# loop-rs232o.net
KiCad netlist of a schematic drawn in EAGLE
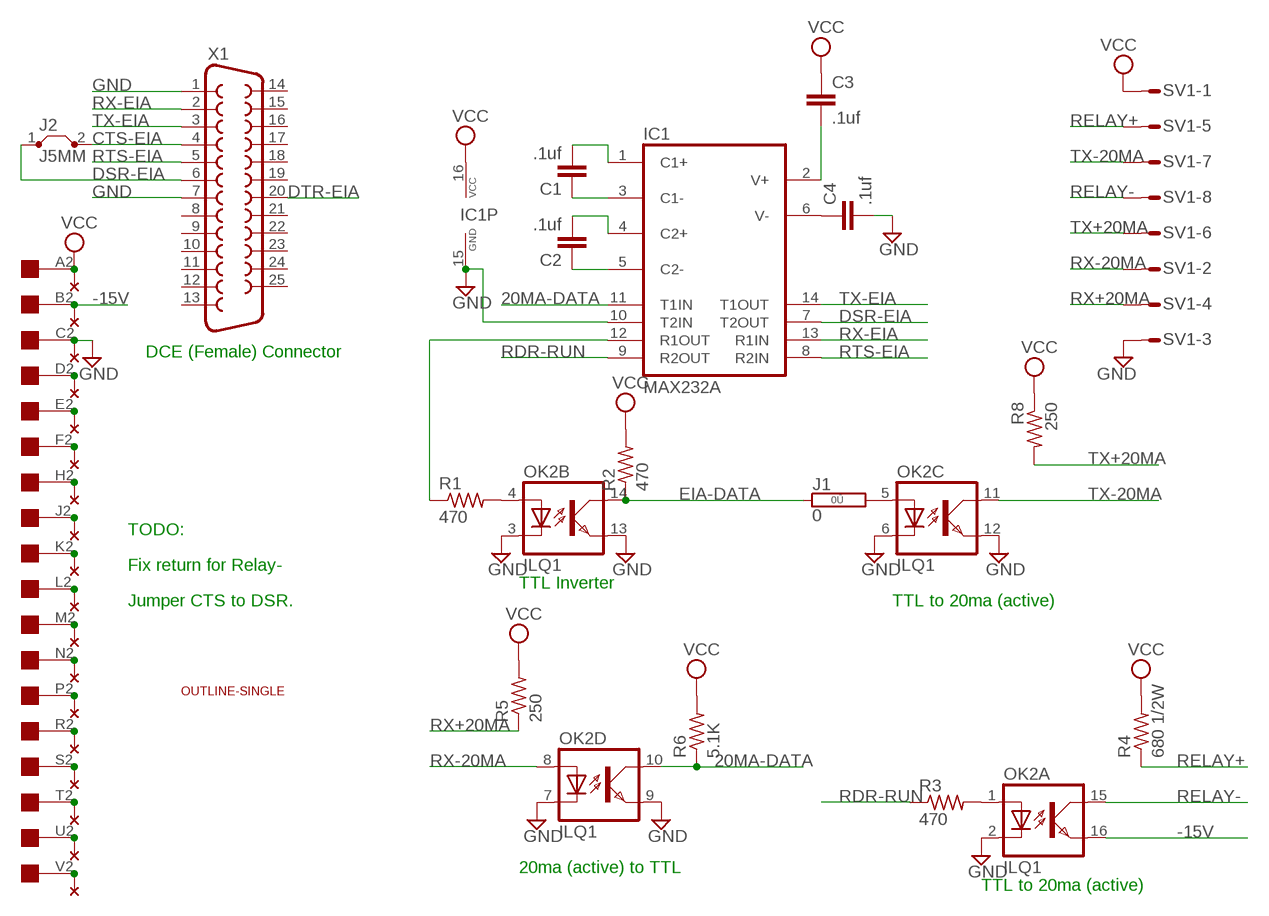
[diagram p0: schematic, sheet 1]

(export (version "E")
  (design (tool "Eeschema 10.0.6"))
  (components
    (comp (ref "C1")
      (value ".1uf")
      (footprint "eagle-import:C050-025X075")
      (libsource (lib "eagle-import") (part "C-EU050-025X075"))
    )
    (comp (ref "C2")
      (value ".1uf")
      (footprint "eagle-import:C050-025X075")
      (libsource (lib "eagle-import") (part "C-EU050-025X075"))
    )
    (comp (ref "C3")
      (value ".1uf")
      (footprint "eagle-import:C050-025X075")
      (libsource (lib "eagle-import") (part "C-EU050-025X075"))
    )
    (comp (ref "C4")
      (value ".1uf")
      (footprint "eagle-import:C050-025X075")
      (libsource (lib "eagle-import") (part "C-EU050-025X075"))
    )
    (comp (ref "IC1")
      (value "MAX232A")
      (footprint "eagle-import:DIL16")
      (fields (field (name "MF") "MAXIM") (field (name "MPN") "MAX232ACPE+"))
      (libsource (lib "eagle-import") (part "MAX232"))
    )
    (comp (ref "J1")
      (value "0")
      (footprint "eagle-import:0R_10")
      (libsource (lib "eagle-import") (part "0R"))
    )
    (comp (ref "J2")
      (value "J5MM")
      (footprint "eagle-import:05")
      (libsource (lib "eagle-import") (part "J5MM"))
    )
    (comp (ref "OK2")
      (value "ILQ1")
      (footprint "eagle-import:DIL16")
      (fields (field (name "MF") "VISHAY/TELEFUNKEN"))
      (libsource (lib "eagle-import") (part "ILQ1"))
    )
    (comp (ref "R1")
      (value "470")
      (footprint "eagle-import:0207_10")
      (libsource (lib "eagle-import") (part "R-US_0207/10"))
    )
    (comp (ref "R2")
      (value "470")
      (footprint "eagle-import:0207_10")
      (libsource (lib "eagle-import") (part "R-US_0207/10"))
    )
    (comp (ref "R3")
      (value "470")
      (footprint "eagle-import:0207_10")
      (libsource (lib "eagle-import") (part "R-US_0207/10"))
    )
    (comp (ref "R4")
      (value "680 1/2W")
      (footprint "eagle-import:0207_10")
      (libsource (lib "eagle-import") (part "R-US_0207/10"))
    )
    (comp (ref "R5")
      (value "250")
      (footprint "eagle-import:0207_10")
      (libsource (lib "eagle-import") (part "R-US_0207/10"))
    )
    (comp (ref "R6")
      (value "5.1K")
      (footprint "eagle-import:0207_10")
      (libsource (lib "eagle-import") (part "R-US_0207/10"))
    )
    (comp (ref "R8")
      (value "250")
      (footprint "eagle-import:0207_10")
      (libsource (lib "eagle-import") (part "R-US_0207/10"))
    )
    (comp (ref "SV1")
      (value "S08P")
      (footprint "eagle-import:S08P")
      (libsource (lib "eagle-import") (part "S08P"))
    )
    (comp (ref "U$2")
      (value "THRU-HOLE1")
      (footprint "eagle-import:THRU-HOLE1")
      (libsource (lib "eagle-import") (part "THRU-HOLE1"))
    )
    (comp (ref "U$3")
      (value "OUTLINE-SINGLE")
      (footprint "eagle-import:SINGLE")
      (libsource (lib "eagle-import") (part "OUTLINE-SINGLE"))
    )
    (comp (ref "U$4")
      (value "EDGE-1")
      (footprint "eagle-import:EDGE-CON1")
      (libsource (lib "eagle-import") (part "EDGE-1"))
    )
    (comp (ref "X1")
      (value "F25H")
      (footprint "eagle-import:F25H")
      (libsource (lib "eagle-import") (part "F25H"))
    )
  )
  (nets
    (net (code "1") (name "/-15V") (class "Default")
      (node (ref "OK2") (pin "16") (pinfunction "EMIT_16") (pintype "passive"))
      (node (ref "U$2") (pin "B2") (pinfunction "P$1_B2") (pintype "passive"))
      (node (ref "U$4") (pin "B2") (pinfunction "1_B2") (pintype "bidirectional"))
    )
    (net (code "2") (name "/20MA-DATA") (class "Default")
      (node (ref "IC1") (pin "11") (pinfunction "T1IN_11") (pintype "input"))
      (node (ref "OK2") (pin "10") (pinfunction "COL_10") (pintype "passive"))
      (node (ref "R6") (pin "1") (pinfunction "1_1") (pintype "passive"))
    )
    (net (code "3") (name "/CTS-EIA") (class "Default")
      (node (ref "J2") (pin "2") (pinfunction "2_2") (pintype "passive"))
      (node (ref "X1") (pin "4") (pinfunction "4_4") (pintype "passive"))
    )
    (net (code "4") (name "/DSR-EIA") (class "Default")
      (node (ref "IC1") (pin "7") (pinfunction "T2OUT_7") (pintype "output"))
      (node (ref "J2") (pin "1") (pinfunction "1_1") (pintype "passive"))
      (node (ref "X1") (pin "6") (pinfunction "6_6") (pintype "passive"))
    )
    (net (code "5") (name "/DTR-EIA") (class "Default")
      (node (ref "X1") (pin "20") (pinfunction "20_20") (pintype "passive"))
    )
    (net (code "6") (name "/EIA-DATA") (class "Default")
      (node (ref "J1") (pin "1") (pinfunction "1_1") (pintype "passive"))
      (node (ref "OK2") (pin "14") (pinfunction "COL_14") (pintype "passive"))
      (node (ref "R2") (pin "1") (pinfunction "1_1") (pintype "passive"))
    )
    (net (code "7") (name "/RDR-RUN") (class "Default")
      (node (ref "IC1") (pin "9") (pinfunction "R2OUT_9") (pintype "output"))
      (node (ref "R3") (pin "1") (pinfunction "1_1") (pintype "passive"))
    )
    (net (code "8") (name "/RELAY+") (class "Default")
      (node (ref "R4") (pin "1") (pinfunction "1_1") (pintype "passive"))
      (node (ref "SV1") (pin "5") (pinfunction "S_5") (pintype "passive"))
    )
    (net (code "9") (name "/RELAY-") (class "Default")
      (node (ref "OK2") (pin "15") (pinfunction "COL_15") (pintype "passive"))
      (node (ref "SV1") (pin "8") (pinfunction "S_8") (pintype "passive"))
    )
    (net (code "10") (name "/RTS-EIA") (class "Default")
      (node (ref "IC1") (pin "8") (pinfunction "R2IN_8") (pintype "input"))
      (node (ref "X1") (pin "5") (pinfunction "5_5") (pintype "passive"))
    )
    (net (code "11") (name "/RX+20MA") (class "Default")
      (node (ref "R5") (pin "1") (pinfunction "1_1") (pintype "passive"))
      (node (ref "SV1") (pin "4") (pinfunction "S_4") (pintype "passive"))
    )
    (net (code "12") (name "/RX-20MA") (class "Default")
      (node (ref "OK2") (pin "8") (pinfunction "A_8") (pintype "passive"))
      (node (ref "SV1") (pin "2") (pinfunction "S_2") (pintype "passive"))
    )
    (net (code "13") (name "/RX-EIA") (class "Default")
      (node (ref "IC1") (pin "13") (pinfunction "R1IN_13") (pintype "input"))
      (node (ref "X1") (pin "2") (pinfunction "2_2") (pintype "passive"))
    )
    (net (code "14") (name "/TX+20MA") (class "Default")
      (node (ref "R8") (pin "2") (pinfunction "2_2") (pintype "passive"))
      (node (ref "SV1") (pin "6") (pinfunction "S_6") (pintype "passive"))
    )
    (net (code "15") (name "/TX-20MA") (class "Default")
      (node (ref "OK2") (pin "11") (pinfunction "COL_11") (pintype "passive"))
      (node (ref "SV1") (pin "7") (pinfunction "S_7") (pintype "passive"))
    )
    (net (code "16") (name "/TX-EIA") (class "Default")
      (node (ref "IC1") (pin "14") (pinfunction "T1OUT_14") (pintype "output"))
      (node (ref "X1") (pin "3") (pinfunction "3_3") (pintype "passive"))
    )
    (net (code "17") (name "GND") (class "Default")
      (node (ref "C4") (pin "2") (pinfunction "2_2") (pintype "passive"))
      (node (ref "IC1") (pin "10") (pinfunction "T2IN_10") (pintype "input"))
      (node (ref "IC1") (pin "15") (pinfunction "GND_15") (pintype "power_in"))
      (node (ref "OK2") (pin "12") (pinfunction "EMIT_12") (pintype "passive"))
      (node (ref "OK2") (pin "13") (pinfunction "EMIT_13") (pintype "passive"))
      (node (ref "OK2") (pin "2") (pinfunction "C_2") (pintype "passive"))
      (node (ref "OK2") (pin "3") (pinfunction "C_3") (pintype "passive"))
      (node (ref "OK2") (pin "6") (pinfunction "C_6") (pintype "passive"))
      (node (ref "OK2") (pin "7") (pinfunction "C_7") (pintype "passive"))
      (node (ref "OK2") (pin "9") (pinfunction "EMIT_9") (pintype "passive"))
      (node (ref "SV1") (pin "3") (pinfunction "S_3") (pintype "passive"))
      (node (ref "U$2") (pin "C2") (pinfunction "P$1_C2") (pintype "passive"))
      (node (ref "U$4") (pin "C2") (pinfunction "1_C2") (pintype "bidirectional"))
      (node (ref "X1") (pin "1") (pinfunction "1_1") (pintype "passive"))
      (node (ref "X1") (pin "7") (pinfunction "7_7") (pintype "passive"))
    )
    (net (code "18") (name "Net-(IC1A-C1+)") (class "Default")
      (node (ref "C1") (pin "2") (pinfunction "2_2") (pintype "passive"))
      (node (ref "IC1") (pin "1") (pinfunction "C1+_1") (pintype "bidirectional"))
    )
    (net (code "19") (name "Net-(IC1A-C1-)") (class "Default")
      (node (ref "C1") (pin "1") (pinfunction "1_1") (pintype "passive"))
      (node (ref "IC1") (pin "3") (pinfunction "C1-_3") (pintype "bidirectional"))
    )
    (net (code "20") (name "Net-(IC1A-C2+)") (class "Default")
      (node (ref "C2") (pin "2") (pinfunction "2_2") (pintype "passive"))
      (node (ref "IC1") (pin "4") (pinfunction "C2+_4") (pintype "bidirectional"))
    )
    (net (code "21") (name "Net-(IC1A-C2-)") (class "Default")
      (node (ref "C2") (pin "1") (pinfunction "1_1") (pintype "passive"))
      (node (ref "IC1") (pin "5") (pinfunction "C2-_5") (pintype "bidirectional"))
    )
    (net (code "22") (name "Net-(IC1A-R1OUT)") (class "Default")
      (node (ref "IC1") (pin "12") (pinfunction "R1OUT_12") (pintype "output"))
      (node (ref "R1") (pin "1") (pinfunction "1_1") (pintype "passive"))
    )
    (net (code "23") (name "Net-(IC1A-V+)") (class "Default")
      (node (ref "C3") (pin "2") (pinfunction "2_2") (pintype "passive"))
      (node (ref "IC1") (pin "2") (pinfunction "V+_2") (pintype "bidirectional"))
    )
    (net (code "24") (name "Net-(IC1A-V-)") (class "Default")
      (node (ref "C4") (pin "1") (pinfunction "1_1") (pintype "passive"))
      (node (ref "IC1") (pin "6") (pinfunction "V-_6") (pintype "bidirectional"))
    )
    (net (code "25") (name "Net-(OK2A-A)") (class "Default")
      (node (ref "OK2") (pin "1") (pinfunction "A_1") (pintype "passive"))
      (node (ref "R3") (pin "2") (pinfunction "2_2") (pintype "passive"))
    )
    (net (code "26") (name "Net-(OK2B-A)") (class "Default")
      (node (ref "OK2") (pin "4") (pinfunction "A_4") (pintype "passive"))
      (node (ref "R1") (pin "2") (pinfunction "2_2") (pintype "passive"))
    )
    (net (code "27") (name "Net-(OK2C-A)") (class "Default")
      (node (ref "J1") (pin "2") (pinfunction "2_2") (pintype "passive"))
      (node (ref "OK2") (pin "5") (pinfunction "A_5") (pintype "passive"))
    )
    (net (code "28") (name "Net-(U$2D-P$1)") (class "Default")
      (node (ref "U$2") (pin "D2") (pinfunction "P$1_D2") (pintype "passive"))
      (node (ref "U$4") (pin "D2") (pinfunction "1_D2") (pintype "bidirectional"))
    )
    (net (code "29") (name "Net-(U$2E-P$1)") (class "Default")
      (node (ref "U$2") (pin "E2") (pinfunction "P$1_E2") (pintype "passive"))
      (node (ref "U$4") (pin "E2") (pinfunction "1_E2") (pintype "bidirectional"))
    )
    (net (code "30") (name "Net-(U$2F-P$1)") (class "Default")
      (node (ref "U$2") (pin "F2") (pinfunction "P$1_F2") (pintype "passive"))
      (node (ref "U$4") (pin "F2") (pinfunction "1_F2") (pintype "bidirectional"))
    )
    (net (code "31") (name "Net-(U$2G-P$1)") (class "Default")
      (node (ref "U$2") (pin "H2") (pinfunction "P$1_H2") (pintype "passive"))
      (node (ref "U$4") (pin "H2") (pinfunction "1_H2") (pintype "bidirectional"))
    )
    (net (code "32") (name "Net-(U$2H-P$1)") (class "Default")
      (node (ref "U$2") (pin "J2") (pinfunction "P$1_J2") (pintype "passive"))
      (node (ref "U$4") (pin "J2") (pinfunction "1_J2") (pintype "bidirectional"))
    )
    (net (code "33") (name "Net-(U$2I-P$1)") (class "Default")
      (node (ref "U$2") (pin "K2") (pinfunction "P$1_K2") (pintype "passive"))
      (node (ref "U$4") (pin "K2") (pinfunction "1_K2") (pintype "bidirectional"))
    )
    (net (code "34") (name "Net-(U$2J-P$1)") (class "Default")
      (node (ref "U$2") (pin "L2") (pinfunction "P$1_L2") (pintype "passive"))
      (node (ref "U$4") (pin "L2") (pinfunction "1_L2") (pintype "bidirectional"))
    )
    (net (code "35") (name "Net-(U$2K-P$1)") (class "Default")
      (node (ref "U$2") (pin "M2") (pinfunction "P$1_M2") (pintype "passive"))
      (node (ref "U$4") (pin "M2") (pinfunction "1_M2") (pintype "bidirectional"))
    )
    (net (code "36") (name "Net-(U$2L-P$1)") (class "Default")
      (node (ref "U$2") (pin "N2") (pinfunction "P$1_N2") (pintype "passive"))
      (node (ref "U$4") (pin "N2") (pinfunction "1_N2") (pintype "bidirectional"))
    )
    (net (code "37") (name "Net-(U$2M-P$1)") (class "Default")
      (node (ref "U$2") (pin "P2") (pinfunction "P$1_P2") (pintype "passive"))
      (node (ref "U$4") (pin "P2") (pinfunction "1_P2") (pintype "bidirectional"))
    )
    (net (code "38") (name "Net-(U$2N-P$1)") (class "Default")
      (node (ref "U$2") (pin "R2") (pinfunction "P$1_R2") (pintype "passive"))
      (node (ref "U$4") (pin "R2") (pinfunction "1_R2") (pintype "bidirectional"))
    )
    (net (code "39") (name "Net-(U$2O-P$1)") (class "Default")
      (node (ref "U$2") (pin "S2") (pinfunction "P$1_S2") (pintype "passive"))
      (node (ref "U$4") (pin "S2") (pinfunction "1_S2") (pintype "bidirectional"))
    )
    (net (code "40") (name "Net-(U$2P-P$1)") (class "Default")
      (node (ref "U$2") (pin "T2") (pinfunction "P$1_T2") (pintype "passive"))
      (node (ref "U$4") (pin "T2") (pinfunction "1_T2") (pintype "bidirectional"))
    )
    (net (code "41") (name "Net-(U$2Q-P$1)") (class "Default")
      (node (ref "U$2") (pin "U2") (pinfunction "P$1_U2") (pintype "passive"))
      (node (ref "U$4") (pin "U2") (pinfunction "1_U2") (pintype "bidirectional"))
    )
    (net (code "42") (name "Net-(U$2R-P$1)") (class "Default")
      (node (ref "U$2") (pin "V2") (pinfunction "P$1_V2") (pintype "passive"))
      (node (ref "U$4") (pin "V2") (pinfunction "1_V2") (pintype "bidirectional"))
    )
    (net (code "43") (name "VCC") (class "Default")
      (node (ref "C3") (pin "1") (pinfunction "1_1") (pintype "passive"))
      (node (ref "IC1") (pin "16") (pinfunction "VCC_16") (pintype "power_in"))
      (node (ref "R2") (pin "2") (pinfunction "2_2") (pintype "passive"))
      (node (ref "R4") (pin "2") (pinfunction "2_2") (pintype "passive"))
      (node (ref "R5") (pin "2") (pinfunction "2_2") (pintype "passive"))
      (node (ref "R6") (pin "2") (pinfunction "2_2") (pintype "passive"))
      (node (ref "R8") (pin "1") (pinfunction "1_1") (pintype "passive"))
      (node (ref "SV1") (pin "1") (pinfunction "S_1") (pintype "passive"))
      (node (ref "U$2") (pin "A2") (pinfunction "P$1_A2") (pintype "passive"))
      (node (ref "U$4") (pin "A2") (pinfunction "1_A2") (pintype "bidirectional"))
    )
    (net (code "44") (name "unconnected-(X1-Pad8)") (class "Default")
      (node (ref "X1") (pin "8") (pinfunction "8_8") (pintype "passive"))
    )
    (net (code "45") (name "unconnected-(X1-Pad9)") (class "Default")
      (node (ref "X1") (pin "9") (pinfunction "9_9") (pintype "passive"))
    )
    (net (code "46") (name "unconnected-(X1-Pad10)") (class "Default")
      (node (ref "X1") (pin "10") (pinfunction "10_10") (pintype "passive"))
    )
    (net (code "47") (name "unconnected-(X1-Pad11)") (class "Default")
      (node (ref "X1") (pin "11") (pinfunction "11_11") (pintype "passive"))
    )
    (net (code "48") (name "unconnected-(X1-Pad12)") (class "Default")
      (node (ref "X1") (pin "12") (pinfunction "12_12") (pintype "passive"))
    )
    (net (code "49") (name "unconnected-(X1-Pad13)") (class "Default")
      (node (ref "X1") (pin "13") (pinfunction "13_13") (pintype "passive"))
    )
    (net (code "50") (name "unconnected-(X1-Pad14)") (class "Default")
      (node (ref "X1") (pin "14") (pinfunction "14_14") (pintype "passive"))
    )
    (net (code "51") (name "unconnected-(X1-Pad15)") (class "Default")
      (node (ref "X1") (pin "15") (pinfunction "15_15") (pintype "passive"))
    )
    (net (code "52") (name "unconnected-(X1-Pad16)") (class "Default")
      (node (ref "X1") (pin "16") (pinfunction "16_16") (pintype "passive"))
    )
    (net (code "53") (name "unconnected-(X1-Pad17)") (class "Default")
      (node (ref "X1") (pin "17") (pinfunction "17_17") (pintype "passive"))
    )
    (net (code "54") (name "unconnected-(X1-Pad18)") (class "Default")
      (node (ref "X1") (pin "18") (pinfunction "18_18") (pintype "passive"))
    )
    (net (code "55") (name "unconnected-(X1-Pad19)") (class "Default")
      (node (ref "X1") (pin "19") (pinfunction "19_19") (pintype "passive"))
    )
    (net (code "56") (name "unconnected-(X1-Pad21)") (class "Default")
      (node (ref "X1") (pin "21") (pinfunction "21_21") (pintype "passive"))
    )
    (net (code "57") (name "unconnected-(X1-Pad22)") (class "Default")
      (node (ref "X1") (pin "22") (pinfunction "22_22") (pintype "passive"))
    )
    (net (code "58") (name "unconnected-(X1-Pad23)") (class "Default")
      (node (ref "X1") (pin "23") (pinfunction "23_23") (pintype "passive"))
    )
    (net (code "59") (name "unconnected-(X1-Pad24)") (class "Default")
      (node (ref "X1") (pin "24") (pinfunction "24_24") (pintype "passive"))
    )
    (net (code "60") (name "unconnected-(X1-Pad25)") (class "Default")
      (node (ref "X1") (pin "25") (pinfunction "25_25") (pintype "passive"))
    )
  )
)
